# LED3.net
KiCad netlist of a schematic drawn in EAGLE
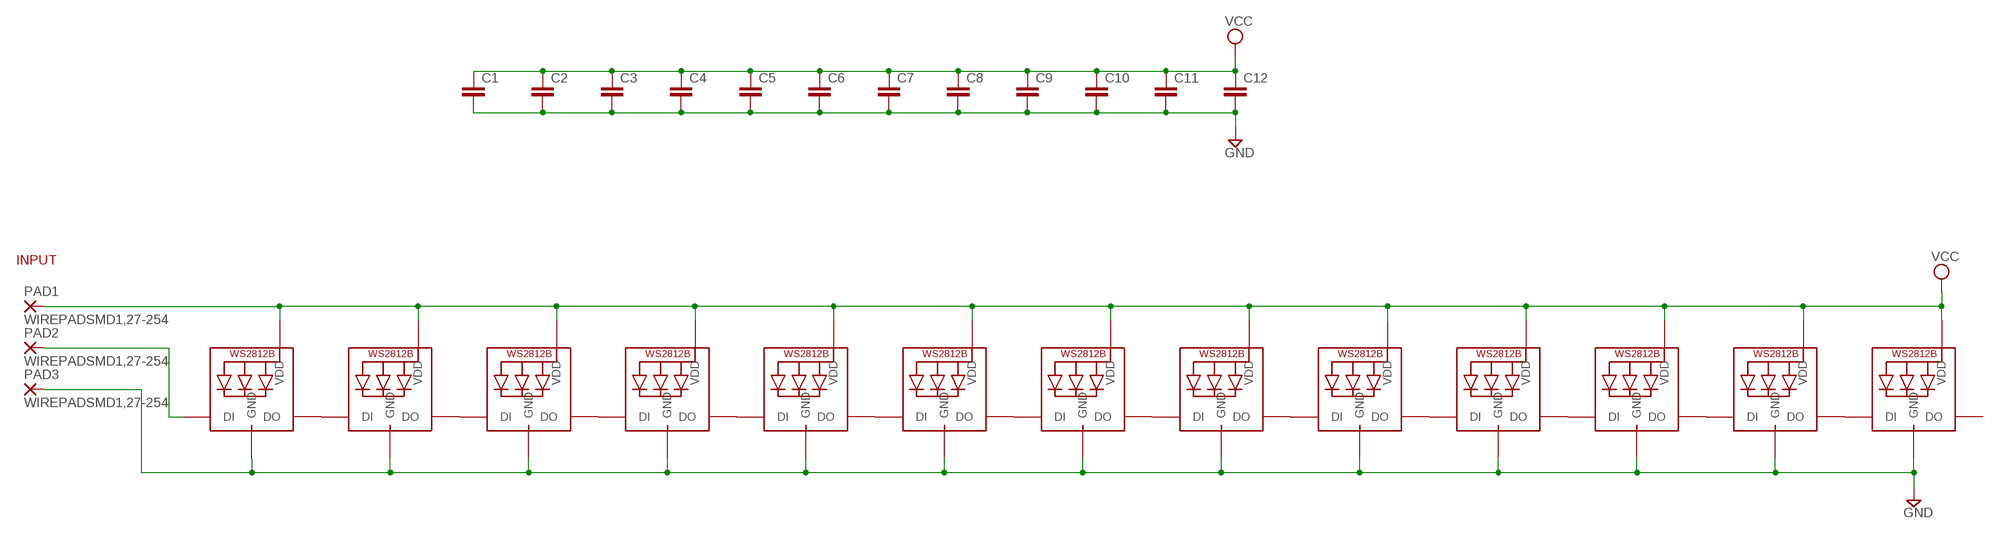
[diagram p0: schematic, sheet 1]

(export (version "E")
  (design (tool "Eeschema 10.0.6"))
  (components
    (comp (ref "C1")
      (value "C-EUC0805K")
      (footprint "eagle-import:C0805K")
      (libsource (lib "eagle-import") (part "C-EUC0805K"))
    )
    (comp (ref "C2")
      (value "C-EUC0805K")
      (footprint "eagle-import:C0805K")
      (libsource (lib "eagle-import") (part "C-EUC0805K"))
    )
    (comp (ref "C3")
      (value "C-EUC0805K")
      (footprint "eagle-import:C0805K")
      (libsource (lib "eagle-import") (part "C-EUC0805K"))
    )
    (comp (ref "C4")
      (value "C-EUC0805K")
      (footprint "eagle-import:C0805K")
      (libsource (lib "eagle-import") (part "C-EUC0805K"))
    )
    (comp (ref "C5")
      (value "C-EUC0805K")
      (footprint "eagle-import:C0805K")
      (libsource (lib "eagle-import") (part "C-EUC0805K"))
    )
    (comp (ref "C6")
      (value "C-EUC0805K")
      (footprint "eagle-import:C0805K")
      (libsource (lib "eagle-import") (part "C-EUC0805K"))
    )
    (comp (ref "C7")
      (value "C-EUC0805K")
      (footprint "eagle-import:C0805K")
      (libsource (lib "eagle-import") (part "C-EUC0805K"))
    )
    (comp (ref "C8")
      (value "C-EUC0805K")
      (footprint "eagle-import:C0805K")
      (libsource (lib "eagle-import") (part "C-EUC0805K"))
    )
    (comp (ref "C9")
      (value "C-EUC0805K")
      (footprint "eagle-import:C0805K")
      (libsource (lib "eagle-import") (part "C-EUC0805K"))
    )
    (comp (ref "C10")
      (value "C-EUC0805K")
      (footprint "eagle-import:C0805K")
      (libsource (lib "eagle-import") (part "C-EUC0805K"))
    )
    (comp (ref "C11")
      (value "C-EUC0805K")
      (footprint "eagle-import:C0805K")
      (libsource (lib "eagle-import") (part "C-EUC0805K"))
    )
    (comp (ref "C12")
      (value "C-EUC0805K")
      (footprint "eagle-import:C0805K")
      (libsource (lib "eagle-import") (part "C-EUC0805K"))
    )
    (comp (ref "LED1")
      (value "WS2812B5050")
      (footprint "eagle-import:WS2812B")
      (libsource (lib "eagle-import") (part "WS2812B5050"))
    )
    (comp (ref "LED2")
      (value "WS2812B5050")
      (footprint "eagle-import:WS2812B")
      (libsource (lib "eagle-import") (part "WS2812B5050"))
    )
    (comp (ref "LED3")
      (value "WS2812B5050")
      (footprint "eagle-import:WS2812B")
      (libsource (lib "eagle-import") (part "WS2812B5050"))
    )
    (comp (ref "LED4")
      (value "WS2812B5050")
      (footprint "eagle-import:WS2812B")
      (libsource (lib "eagle-import") (part "WS2812B5050"))
    )
    (comp (ref "LED5")
      (value "WS2812B5050")
      (footprint "eagle-import:WS2812B")
      (libsource (lib "eagle-import") (part "WS2812B5050"))
    )
    (comp (ref "LED6")
      (value "WS2812B5050")
      (footprint "eagle-import:WS2812B")
      (libsource (lib "eagle-import") (part "WS2812B5050"))
    )
    (comp (ref "LED7")
      (value "WS2812B5050")
      (footprint "eagle-import:WS2812B")
      (libsource (lib "eagle-import") (part "WS2812B5050"))
    )
    (comp (ref "LED8")
      (value "WS2812B5050")
      (footprint "eagle-import:WS2812B")
      (libsource (lib "eagle-import") (part "WS2812B5050"))
    )
    (comp (ref "LED9")
      (value "WS2812B5050")
      (footprint "eagle-import:WS2812B")
      (libsource (lib "eagle-import") (part "WS2812B5050"))
    )
    (comp (ref "LED10")
      (value "WS2812B5050")
      (footprint "eagle-import:WS2812B")
      (libsource (lib "eagle-import") (part "WS2812B5050"))
    )
    (comp (ref "LED11")
      (value "WS2812B5050")
      (footprint "eagle-import:WS2812B")
      (libsource (lib "eagle-import") (part "WS2812B5050"))
    )
    (comp (ref "LED12")
      (value "WS2812B5050")
      (footprint "eagle-import:WS2812B")
      (libsource (lib "eagle-import") (part "WS2812B5050"))
    )
    (comp (ref "LED13")
      (value "WS2812B5050")
      (footprint "eagle-import:WS2812B")
      (libsource (lib "eagle-import") (part "WS2812B5050"))
    )
    (comp (ref "PAD1")
      (value "WIREPADSMD1,27-254")
      (footprint "eagle-import:SMD1,27-2,54")
      (libsource (lib "eagle-import") (part "WIREPADSMD1,27-254"))
    )
    (comp (ref "PAD2")
      (value "WIREPADSMD1,27-254")
      (footprint "eagle-import:SMD1,27-2,54")
      (libsource (lib "eagle-import") (part "WIREPADSMD1,27-254"))
    )
    (comp (ref "PAD3")
      (value "WIREPADSMD1,27-254")
      (footprint "eagle-import:SMD1,27-2,54")
      (libsource (lib "eagle-import") (part "WIREPADSMD1,27-254"))
    )
  )
  (nets
    (net (code "1") (name "GND") (class "Default")
      (node (ref "C1") (pin "2") (pinfunction "2_2") (pintype "passive"))
      (node (ref "C10") (pin "2") (pinfunction "2_2") (pintype "passive"))
      (node (ref "C11") (pin "2") (pinfunction "2_2") (pintype "passive"))
      (node (ref "C12") (pin "2") (pinfunction "2_2") (pintype "passive"))
      (node (ref "C2") (pin "2") (pinfunction "2_2") (pintype "passive"))
      (node (ref "C3") (pin "2") (pinfunction "2_2") (pintype "passive"))
      (node (ref "C4") (pin "2") (pinfunction "2_2") (pintype "passive"))
      (node (ref "C5") (pin "2") (pinfunction "2_2") (pintype "passive"))
      (node (ref "C6") (pin "2") (pinfunction "2_2") (pintype "passive"))
      (node (ref "C7") (pin "2") (pinfunction "2_2") (pintype "passive"))
      (node (ref "C8") (pin "2") (pinfunction "2_2") (pintype "passive"))
      (node (ref "C9") (pin "2") (pinfunction "2_2") (pintype "passive"))
      (node (ref "LED1") (pin "3-GND") (pinfunction "GND_3-GND") (pintype "power_in"))
      (node (ref "LED10") (pin "3-GND") (pinfunction "GND_3-GND") (pintype "power_in"))
      (node (ref "LED11") (pin "3-GND") (pinfunction "GND_3-GND") (pintype "power_in"))
      (node (ref "LED12") (pin "3-GND") (pinfunction "GND_3-GND") (pintype "power_in"))
      (node (ref "LED13") (pin "3-GND") (pinfunction "GND_3-GND") (pintype "power_in"))
      (node (ref "LED2") (pin "3-GND") (pinfunction "GND_3-GND") (pintype "power_in"))
      (node (ref "LED3") (pin "3-GND") (pinfunction "GND_3-GND") (pintype "power_in"))
      (node (ref "LED4") (pin "3-GND") (pinfunction "GND_3-GND") (pintype "power_in"))
      (node (ref "LED5") (pin "3-GND") (pinfunction "GND_3-GND") (pintype "power_in"))
      (node (ref "LED6") (pin "3-GND") (pinfunction "GND_3-GND") (pintype "power_in"))
      (node (ref "LED7") (pin "3-GND") (pinfunction "GND_3-GND") (pintype "power_in"))
      (node (ref "LED8") (pin "3-GND") (pinfunction "GND_3-GND") (pintype "power_in"))
      (node (ref "LED9") (pin "3-GND") (pinfunction "GND_3-GND") (pintype "power_in"))
      (node (ref "PAD3") (pin "1") (pinfunction "P_1") (pintype "passive"))
    )
    (net (code "2") (name "Net-(LED1-DI)") (class "Default")
      (node (ref "LED1") (pin "4-DIN") (pinfunction "DI_4-DIN") (pintype "input"))
      (node (ref "PAD2") (pin "1") (pinfunction "P_1") (pintype "passive"))
    )
    (net (code "3") (name "Net-(LED1-DO)") (class "Default")
      (node (ref "LED1") (pin "2-DOUT") (pinfunction "DO_2-DOUT") (pintype "output"))
      (node (ref "LED2") (pin "4-DIN") (pinfunction "DI_4-DIN") (pintype "input"))
    )
    (net (code "4") (name "Net-(LED2-DO)") (class "Default")
      (node (ref "LED2") (pin "2-DOUT") (pinfunction "DO_2-DOUT") (pintype "output"))
      (node (ref "LED3") (pin "4-DIN") (pinfunction "DI_4-DIN") (pintype "input"))
    )
    (net (code "5") (name "Net-(LED3-DO)") (class "Default")
      (node (ref "LED3") (pin "2-DOUT") (pinfunction "DO_2-DOUT") (pintype "output"))
      (node (ref "LED4") (pin "4-DIN") (pinfunction "DI_4-DIN") (pintype "input"))
    )
    (net (code "6") (name "Net-(LED4-DO)") (class "Default")
      (node (ref "LED4") (pin "2-DOUT") (pinfunction "DO_2-DOUT") (pintype "output"))
      (node (ref "LED5") (pin "4-DIN") (pinfunction "DI_4-DIN") (pintype "input"))
    )
    (net (code "7") (name "Net-(LED5-DO)") (class "Default")
      (node (ref "LED5") (pin "2-DOUT") (pinfunction "DO_2-DOUT") (pintype "output"))
      (node (ref "LED6") (pin "4-DIN") (pinfunction "DI_4-DIN") (pintype "input"))
    )
    (net (code "8") (name "Net-(LED6-DO)") (class "Default")
      (node (ref "LED6") (pin "2-DOUT") (pinfunction "DO_2-DOUT") (pintype "output"))
      (node (ref "LED7") (pin "4-DIN") (pinfunction "DI_4-DIN") (pintype "input"))
    )
    (net (code "9") (name "Net-(LED7-DO)") (class "Default")
      (node (ref "LED7") (pin "2-DOUT") (pinfunction "DO_2-DOUT") (pintype "output"))
      (node (ref "LED8") (pin "4-DIN") (pinfunction "DI_4-DIN") (pintype "input"))
    )
    (net (code "10") (name "Net-(LED8-DO)") (class "Default")
      (node (ref "LED8") (pin "2-DOUT") (pinfunction "DO_2-DOUT") (pintype "output"))
      (node (ref "LED9") (pin "4-DIN") (pinfunction "DI_4-DIN") (pintype "input"))
    )
    (net (code "11") (name "Net-(LED10-DI)") (class "Default")
      (node (ref "LED10") (pin "4-DIN") (pinfunction "DI_4-DIN") (pintype "input"))
      (node (ref "LED9") (pin "2-DOUT") (pinfunction "DO_2-DOUT") (pintype "output"))
    )
    (net (code "12") (name "Net-(LED10-DO)") (class "Default")
      (node (ref "LED10") (pin "2-DOUT") (pinfunction "DO_2-DOUT") (pintype "output"))
      (node (ref "LED11") (pin "4-DIN") (pinfunction "DI_4-DIN") (pintype "input"))
    )
    (net (code "13") (name "Net-(LED11-DO)") (class "Default")
      (node (ref "LED11") (pin "2-DOUT") (pinfunction "DO_2-DOUT") (pintype "output"))
      (node (ref "LED12") (pin "4-DIN") (pinfunction "DI_4-DIN") (pintype "input"))
    )
    (net (code "14") (name "Net-(LED12-DO)") (class "Default")
      (node (ref "LED12") (pin "2-DOUT") (pinfunction "DO_2-DOUT") (pintype "output"))
      (node (ref "LED13") (pin "4-DIN") (pinfunction "DI_4-DIN") (pintype "input"))
    )
    (net (code "15") (name "VCC") (class "Default")
      (node (ref "C1") (pin "1") (pinfunction "1_1") (pintype "passive"))
      (node (ref "C10") (pin "1") (pinfunction "1_1") (pintype "passive"))
      (node (ref "C11") (pin "1") (pinfunction "1_1") (pintype "passive"))
      (node (ref "C12") (pin "1") (pinfunction "1_1") (pintype "passive"))
      (node (ref "C2") (pin "1") (pinfunction "1_1") (pintype "passive"))
      (node (ref "C3") (pin "1") (pinfunction "1_1") (pintype "passive"))
      (node (ref "C4") (pin "1") (pinfunction "1_1") (pintype "passive"))
      (node (ref "C5") (pin "1") (pinfunction "1_1") (pintype "passive"))
      (node (ref "C6") (pin "1") (pinfunction "1_1") (pintype "passive"))
      (node (ref "C7") (pin "1") (pinfunction "1_1") (pintype "passive"))
      (node (ref "C8") (pin "1") (pinfunction "1_1") (pintype "passive"))
      (node (ref "C9") (pin "1") (pinfunction "1_1") (pintype "passive"))
      (node (ref "LED1") (pin "1-VDD") (pinfunction "VDD_1-VDD") (pintype "power_in"))
      (node (ref "LED10") (pin "1-VDD") (pinfunction "VDD_1-VDD") (pintype "power_in"))
      (node (ref "LED11") (pin "1-VDD") (pinfunction "VDD_1-VDD") (pintype "power_in"))
      (node (ref "LED12") (pin "1-VDD") (pinfunction "VDD_1-VDD") (pintype "power_in"))
      (node (ref "LED13") (pin "1-VDD") (pinfunction "VDD_1-VDD") (pintype "power_in"))
      (node (ref "LED2") (pin "1-VDD") (pinfunction "VDD_1-VDD") (pintype "power_in"))
      (node (ref "LED3") (pin "1-VDD") (pinfunction "VDD_1-VDD") (pintype "power_in"))
      (node (ref "LED4") (pin "1-VDD") (pinfunction "VDD_1-VDD") (pintype "power_in"))
      (node (ref "LED5") (pin "1-VDD") (pinfunction "VDD_1-VDD") (pintype "power_in"))
      (node (ref "LED6") (pin "1-VDD") (pinfunction "VDD_1-VDD") (pintype "power_in"))
      (node (ref "LED7") (pin "1-VDD") (pinfunction "VDD_1-VDD") (pintype "power_in"))
      (node (ref "LED8") (pin "1-VDD") (pinfunction "VDD_1-VDD") (pintype "power_in"))
      (node (ref "LED9") (pin "1-VDD") (pinfunction "VDD_1-VDD") (pintype "power_in"))
      (node (ref "PAD1") (pin "1") (pinfunction "P_1") (pintype "passive"))
    )
    (net (code "16") (name "unconnected-(LED13-DO-Pad2-DOUT)") (class "Default")
      (node (ref "LED13") (pin "2-DOUT") (pinfunction "DO_2-DOUT") (pintype "output"))
    )
  )
)
